# ledstringpower_unrouted.net
KiCad netlist of a schematic drawn in EAGLE
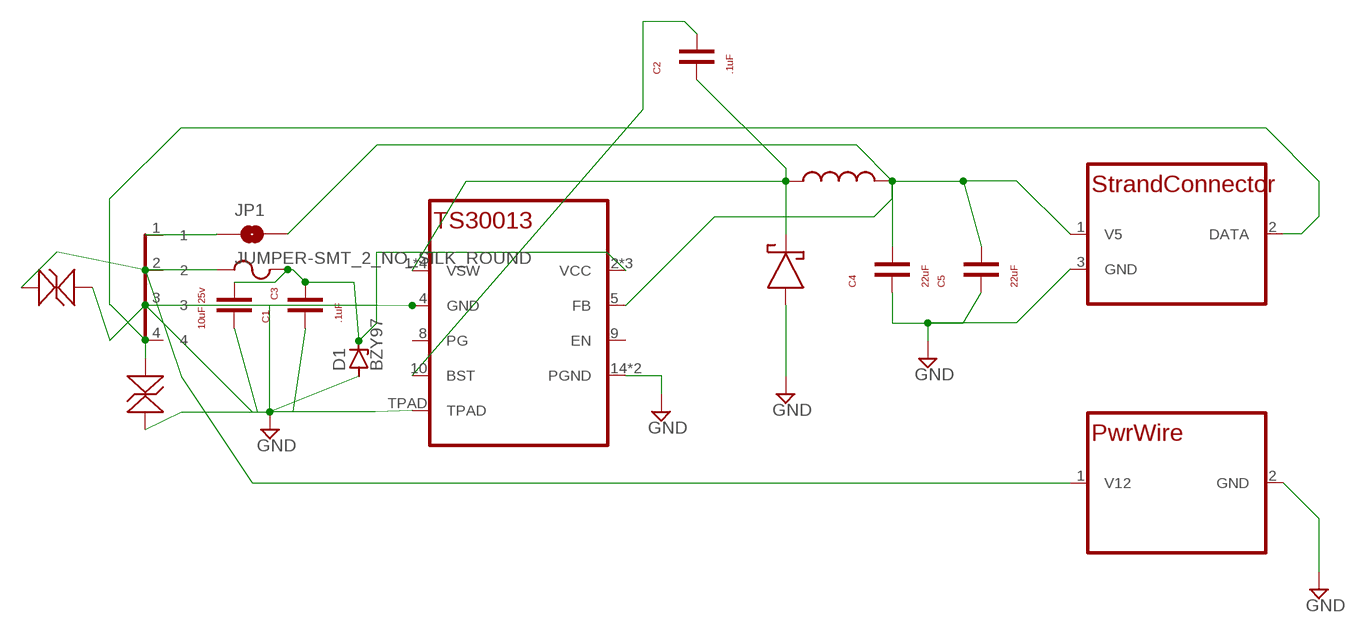
[diagram p0: schematic, sheet 1]

(export (version "E")
  (design (tool "Eeschema 10.0.6"))
  (components
    (comp (ref "C1")
      (value ".1uF")
      (footprint "eagle-import:C0603")
      (libsource (lib "eagle-import") (part "CAPACITOR_NONPOLARC0603"))
    )
    (comp (ref "C2")
      (value ".1uF")
      (footprint "eagle-import:C0603")
      (libsource (lib "eagle-import") (part "CAPACITOR_NONPOLARC0603"))
    )
    (comp (ref "C3")
      (value "10uF 25v")
      (footprint "eagle-import:C1206")
      (libsource (lib "eagle-import") (part "CL31A106MAHNNNEC1206"))
    )
    (comp (ref "C4")
      (value "22uF")
      (footprint "eagle-import:C0603")
      (libsource (lib "eagle-import") (part "GRM188R61A226ME15DC0603"))
    )
    (comp (ref "C5")
      (value "22uF")
      (footprint "eagle-import:C0603")
      (libsource (lib "eagle-import") (part "GRM188R61A226ME15DC0603"))
    )
    (comp (ref "D1")
      (value "BZY97")
      (footprint "eagle-import:F126Z12")
      (libsource (lib "eagle-import") (part "BZY97"))
    )
    (comp (ref "D2")
      (value "LS54LS54")
      (footprint "eagle-import:LS54")
      (libsource (lib "eagle-import") (part "LS54LS54"))
    )
    (comp (ref "F1")
      (value "3A")
      (footprint "eagle-import:R0603")
      (libsource (lib "eagle-import") (part "FUSER0603"))
    )
    (comp (ref "IC1")
      (value "TS30013QFN16")
      (footprint "eagle-import:QFN16")
      (libsource (lib "eagle-import") (part "TS30013QFN16"))
    )
    (comp (ref "JP1")
      (value "JUMPER-SMT_2_NO_SILK_ROUND")
      (footprint "eagle-import:SMT-JUMPER_2_NO_SILK_ROUND")
      (libsource (lib "eagle-import") (part "JUMPER-SMT_2_NO_SILK_ROUND"))
    )
    (comp (ref "L1")
      (value "SRN5040TA-4R7MSRN5040TA")
      (footprint "eagle-import:SRN5040TA")
      (libsource (lib "eagle-import") (part "SRN5040TA-4R7MSRN5040TA"))
    )
    (comp (ref "TVS1")
      (value "DESD5V0U1BL-7BDFN1006-2")
      (footprint "eagle-import:DFN1006-2")
      (libsource (lib "eagle-import") (part "DESD5V0U1BL-7BDFN1006-2"))
    )
    (comp (ref "TVS2")
      (value "DESD5V0U1BL-7BDFN1006-2")
      (footprint "eagle-import:DFN1006-2")
      (libsource (lib "eagle-import") (part "DESD5V0U1BL-7BDFN1006-2"))
    )
    (comp (ref "U$3")
      (value "TE-1969806-1TE-1969806-1")
      (footprint "eagle-import:TE-1969806-1")
      (libsource (lib "eagle-import") (part "TE-1969806-1TE-1969806-1"))
    )
    (comp (ref "U$5")
      (value "LEDSTRANDDLEDWIREP")
      (footprint "eagle-import:LEDWIREP")
      (libsource (lib "eagle-import") (part "LEDSTRANDDLEDWIREP"))
    )
    (comp (ref "U$8")
      (value "PWRWIREDPWRWIREP")
      (footprint "eagle-import:PWRWIREP")
      (libsource (lib "eagle-import") (part "PWRWIREDPWRWIREP"))
    )
  )
  (nets
    (net (code "1") (name "GND") (class "Default")
      (node (ref "C1") (pin "1") (pinfunction "1_1") (pintype "bidirectional"))
      (node (ref "C3") (pin "2") (pinfunction "2_2") (pintype "bidirectional"))
      (node (ref "C4") (pin "1") (pinfunction "1_1") (pintype "bidirectional"))
      (node (ref "C5") (pin "1") (pinfunction "1_1") (pintype "bidirectional"))
      (node (ref "D1") (pin "A") (pinfunction "A_A") (pintype "passive"))
      (node (ref "D2") (pin "1") (pinfunction "1_1") (pintype "bidirectional"))
      (node (ref "IC1") (pin "14") (pinfunction "PGND_14") (pintype "bidirectional"))
      (node (ref "IC1") (pin "15") (pinfunction "PGND_15") (pintype "bidirectional"))
      (node (ref "IC1") (pin "4") (pinfunction "GND_4") (pintype "bidirectional"))
      (node (ref "IC1") (pin "TPAD") (pinfunction "TPAD_TPAD") (pintype "bidirectional"))
      (node (ref "TVS1") (pin "1") (pinfunction "1_1") (pintype "bidirectional"))
      (node (ref "TVS2") (pin "1") (pinfunction "1_1") (pintype "bidirectional"))
      (node (ref "U$3") (pin "3") (pinfunction "3_3") (pintype "bidirectional"))
      (node (ref "U$5") (pin "3") (pinfunction "GND_3") (pintype "bidirectional"))
      (node (ref "U$8") (pin "2") (pinfunction "GND_2") (pintype "bidirectional"))
    )
    (net (code "2") (name "Net-(C1-Pad2)") (class "Default")
      (node (ref "C1") (pin "2") (pinfunction "2_2") (pintype "bidirectional"))
      (node (ref "C3") (pin "1") (pinfunction "1_1") (pintype "bidirectional"))
      (node (ref "D1") (pin "C") (pinfunction "C_C") (pintype "passive"))
      (node (ref "F1") (pin "2") (pinfunction "2_2") (pintype "bidirectional"))
      (node (ref "IC1") (pin "11") (pinfunction "VCC_11") (pintype "bidirectional"))
      (node (ref "IC1") (pin "2") (pinfunction "VCC_2") (pintype "bidirectional"))
      (node (ref "IC1") (pin "3") (pinfunction "VCC_3") (pintype "bidirectional"))
    )
    (net (code "3") (name "Net-(C2-Pad1)") (class "Default")
      (node (ref "C2") (pin "1") (pinfunction "1_1") (pintype "bidirectional"))
      (node (ref "D2") (pin "2") (pinfunction "2_2") (pintype "bidirectional"))
      (node (ref "IC1") (pin "1") (pinfunction "VSW_1") (pintype "bidirectional"))
      (node (ref "IC1") (pin "12") (pinfunction "VSW_12") (pintype "bidirectional"))
      (node (ref "IC1") (pin "13") (pinfunction "VSW_13") (pintype "bidirectional"))
      (node (ref "IC1") (pin "16") (pinfunction "VSW_16") (pintype "bidirectional"))
      (node (ref "L1") (pin "1") (pinfunction "1_1") (pintype "bidirectional"))
    )
    (net (code "4") (name "Net-(IC1-BST)") (class "Default")
      (node (ref "C2") (pin "2") (pinfunction "2_2") (pintype "bidirectional"))
      (node (ref "IC1") (pin "10") (pinfunction "BST_10") (pintype "bidirectional"))
    )
    (net (code "5") (name "Net-(IC1-FB)") (class "Default")
      (node (ref "C4") (pin "2") (pinfunction "2_2") (pintype "bidirectional"))
      (node (ref "C5") (pin "2") (pinfunction "2_2") (pintype "bidirectional"))
      (node (ref "IC1") (pin "5") (pinfunction "FB_5") (pintype "bidirectional"))
      (node (ref "JP1") (pin "2") (pinfunction "2_2") (pintype "passive"))
      (node (ref "L1") (pin "2") (pinfunction "2_2") (pintype "bidirectional"))
      (node (ref "U$5") (pin "1") (pinfunction "V5_1") (pintype "bidirectional"))
    )
    (net (code "6") (name "Net-(JP1-Pad1)") (class "Default")
      (node (ref "JP1") (pin "1") (pinfunction "1_1") (pintype "passive"))
      (node (ref "U$3") (pin "1") (pinfunction "1_1") (pintype "bidirectional"))
    )
    (net (code "7") (name "Net-(U$5-DATA)") (class "Default")
      (node (ref "TVS2") (pin "2") (pinfunction "2_2") (pintype "bidirectional"))
      (node (ref "U$3") (pin "4") (pinfunction "4_4") (pintype "bidirectional"))
      (node (ref "U$5") (pin "2") (pinfunction "DATA_2") (pintype "bidirectional"))
    )
    (net (code "8") (name "Net-(U$8-V12)") (class "Default")
      (node (ref "F1") (pin "1") (pinfunction "1_1") (pintype "bidirectional"))
      (node (ref "TVS1") (pin "2") (pinfunction "2_2") (pintype "bidirectional"))
      (node (ref "U$3") (pin "2") (pinfunction "2_2") (pintype "bidirectional"))
      (node (ref "U$8") (pin "1") (pinfunction "V12_1") (pintype "bidirectional"))
    )
    (net (code "9") (name "unconnected-(IC1-EN-Pad9)") (class "Default")
      (node (ref "IC1") (pin "9") (pinfunction "EN_9") (pintype "bidirectional"))
    )
    (net (code "10") (name "unconnected-(IC1-PG-Pad8)") (class "Default")
      (node (ref "IC1") (pin "8") (pinfunction "PG_8") (pintype "bidirectional"))
    )
  )
)
